# Power_Board.net
KiCad netlist of a schematic drawn in EAGLE
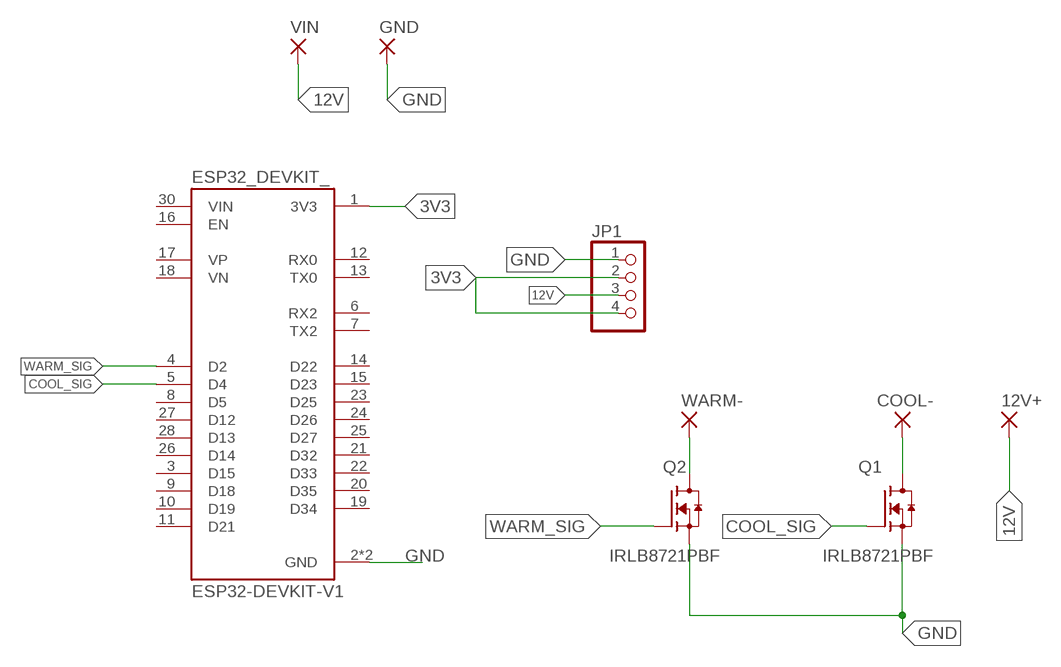
[diagram p0: schematic, sheet 1]

(export (version "E")
  (design (tool "Eeschema 10.0.6"))
  (components
    (comp (ref "12V+")
      (value "WIREPADSMD5-2,5")
      (footprint "eagle-import:5-2,5")
      (libsource (lib "eagle-import") (part "WIREPADSMD5-2,5"))
    )
    (comp (ref "COOL-")
      (value "WIREPADSMD5-2,5")
      (footprint "eagle-import:5-2,5")
      (libsource (lib "eagle-import") (part "WIREPADSMD5-2,5"))
    )
    (comp (ref "ESP32_DEVKIT_")
      (value "ESP32-DEVKIT-V1")
      (footprint "eagle-import:MODULE_ESP32_DEVKIT_V1")
      (fields (field (name "MF") "Do it"))
      (libsource (lib "eagle-import") (part "ESP32-DEVKIT-V1"))
    )
    (comp (ref "GND")
      (value "WIREPADSMD5-2,5")
      (footprint "eagle-import:5-2,5")
      (libsource (lib "eagle-import") (part "WIREPADSMD5-2,5"))
    )
    (comp (ref "JP1")
      (value "PINHD-1X4")
      (footprint "eagle-import:1X04")
      (libsource (lib "eagle-import") (part "PINHD-1X4"))
    )
    (comp (ref "Q1")
      (value "IRLB8721PBF")
      (footprint "eagle-import:TO254P1067X483X2057-3")
      (fields (field (name "MF") "Infineon Technologies"))
      (libsource (lib "eagle-import") (part "IRLB8721PBF"))
    )
    (comp (ref "Q2")
      (value "IRLB8721PBF")
      (footprint "eagle-import:TO254P1067X483X2057-3")
      (fields (field (name "MF") "Infineon Technologies"))
      (libsource (lib "eagle-import") (part "IRLB8721PBF"))
    )
    (comp (ref "VIN")
      (value "WIREPADSMD5-2,5")
      (footprint "eagle-import:5-2,5")
      (libsource (lib "eagle-import") (part "WIREPADSMD5-2,5"))
    )
    (comp (ref "WARM-")
      (value "WIREPADSMD5-2,5")
      (footprint "eagle-import:5-2,5")
      (libsource (lib "eagle-import") (part "WIREPADSMD5-2,5"))
    )
  )
  (nets
    (net (code "1") (name "3V3") (class "Default")
      (node (ref "ESP32_DEVKIT_") (pin "1") (pinfunction "3V3_1") (pintype "output"))
      (node (ref "JP1") (pin "2") (pinfunction "2_2") (pintype "passive"))
      (node (ref "JP1") (pin "4") (pinfunction "4_4") (pintype "passive"))
    )
    (net (code "2") (name "12V") (class "Default")
      (node (ref "12V+") (pin "1") (pinfunction "P_1") (pintype "passive"))
      (node (ref "JP1") (pin "3") (pinfunction "3_3") (pintype "passive"))
      (node (ref "VIN") (pin "1") (pinfunction "P_1") (pintype "passive"))
    )
    (net (code "3") (name "COOL_SIG") (class "Default")
      (node (ref "ESP32_DEVKIT_") (pin "5") (pinfunction "D4_5") (pintype "bidirectional"))
      (node (ref "Q1") (pin "1") (pinfunction "G_1") (pintype "passive"))
    )
    (net (code "4") (name "GND") (class "Default")
      (node (ref "ESP32_DEVKIT_") (pin "2") (pinfunction "GND_2") (pintype "power_in"))
      (node (ref "ESP32_DEVKIT_") (pin "29") (pinfunction "GND_29") (pintype "power_in"))
      (node (ref "GND") (pin "1") (pinfunction "P_1") (pintype "passive"))
      (node (ref "JP1") (pin "1") (pinfunction "1_1") (pintype "passive"))
      (node (ref "Q1") (pin "3") (pinfunction "S_3") (pintype "passive"))
      (node (ref "Q2") (pin "3") (pinfunction "S_3") (pintype "passive"))
    )
    (net (code "5") (name "Net-(COOL--P)") (class "Default")
      (node (ref "COOL-") (pin "1") (pinfunction "P_1") (pintype "passive"))
      (node (ref "Q1") (pin "2") (pinfunction "D_2") (pintype "passive"))
    )
    (net (code "6") (name "Net-(Q2-D)") (class "Default")
      (node (ref "Q2") (pin "2") (pinfunction "D_2") (pintype "passive"))
      (node (ref "WARM-") (pin "1") (pinfunction "P_1") (pintype "passive"))
    )
    (net (code "7") (name "WARM_SIG") (class "Default")
      (node (ref "ESP32_DEVKIT_") (pin "4") (pinfunction "D2_4") (pintype "bidirectional"))
      (node (ref "Q2") (pin "1") (pinfunction "G_1") (pintype "passive"))
    )
    (net (code "8") (name "unconnected-(ESP32_DEVKIT_-D5-Pad8)") (class "Default")
      (node (ref "ESP32_DEVKIT_") (pin "8") (pinfunction "D5_8") (pintype "bidirectional"))
    )
    (net (code "9") (name "unconnected-(ESP32_DEVKIT_-D12-Pad27)") (class "Default")
      (node (ref "ESP32_DEVKIT_") (pin "27") (pinfunction "D12_27") (pintype "bidirectional"))
    )
    (net (code "10") (name "unconnected-(ESP32_DEVKIT_-D13-Pad28)") (class "Default")
      (node (ref "ESP32_DEVKIT_") (pin "28") (pinfunction "D13_28") (pintype "bidirectional"))
    )
    (net (code "11") (name "unconnected-(ESP32_DEVKIT_-D14-Pad26)") (class "Default")
      (node (ref "ESP32_DEVKIT_") (pin "26") (pinfunction "D14_26") (pintype "bidirectional"))
    )
    (net (code "12") (name "unconnected-(ESP32_DEVKIT_-D15-Pad3)") (class "Default")
      (node (ref "ESP32_DEVKIT_") (pin "3") (pinfunction "D15_3") (pintype "bidirectional"))
    )
    (net (code "13") (name "unconnected-(ESP32_DEVKIT_-D18-Pad9)") (class "Default")
      (node (ref "ESP32_DEVKIT_") (pin "9") (pinfunction "D18_9") (pintype "bidirectional"))
    )
    (net (code "14") (name "unconnected-(ESP32_DEVKIT_-D19-Pad10)") (class "Default")
      (node (ref "ESP32_DEVKIT_") (pin "10") (pinfunction "D19_10") (pintype "bidirectional"))
    )
    (net (code "15") (name "unconnected-(ESP32_DEVKIT_-D21-Pad11)") (class "Default")
      (node (ref "ESP32_DEVKIT_") (pin "11") (pinfunction "D21_11") (pintype "bidirectional"))
    )
    (net (code "16") (name "unconnected-(ESP32_DEVKIT_-D22-Pad14)") (class "Default")
      (node (ref "ESP32_DEVKIT_") (pin "14") (pinfunction "D22_14") (pintype "bidirectional"))
    )
    (net (code "17") (name "unconnected-(ESP32_DEVKIT_-D23-Pad15)") (class "Default")
      (node (ref "ESP32_DEVKIT_") (pin "15") (pinfunction "D23_15") (pintype "bidirectional"))
    )
    (net (code "18") (name "unconnected-(ESP32_DEVKIT_-D25-Pad23)") (class "Default")
      (node (ref "ESP32_DEVKIT_") (pin "23") (pinfunction "D25_23") (pintype "bidirectional"))
    )
    (net (code "19") (name "unconnected-(ESP32_DEVKIT_-D26-Pad24)") (class "Default")
      (node (ref "ESP32_DEVKIT_") (pin "24") (pinfunction "D26_24") (pintype "bidirectional"))
    )
    (net (code "20") (name "unconnected-(ESP32_DEVKIT_-D27-Pad25)") (class "Default")
      (node (ref "ESP32_DEVKIT_") (pin "25") (pinfunction "D27_25") (pintype "bidirectional"))
    )
    (net (code "21") (name "unconnected-(ESP32_DEVKIT_-D32-Pad21)") (class "Default")
      (node (ref "ESP32_DEVKIT_") (pin "21") (pinfunction "D32_21") (pintype "bidirectional"))
    )
    (net (code "22") (name "unconnected-(ESP32_DEVKIT_-D33-Pad22)") (class "Default")
      (node (ref "ESP32_DEVKIT_") (pin "22") (pinfunction "D33_22") (pintype "bidirectional"))
    )
    (net (code "23") (name "unconnected-(ESP32_DEVKIT_-D34-Pad19)") (class "Default")
      (node (ref "ESP32_DEVKIT_") (pin "19") (pinfunction "D34_19") (pintype "bidirectional"))
    )
    (net (code "24") (name "unconnected-(ESP32_DEVKIT_-D35-Pad20)") (class "Default")
      (node (ref "ESP32_DEVKIT_") (pin "20") (pinfunction "D35_20") (pintype "bidirectional"))
    )
    (net (code "25") (name "unconnected-(ESP32_DEVKIT_-EN-Pad16)") (class "Default")
      (node (ref "ESP32_DEVKIT_") (pin "16") (pinfunction "EN_16") (pintype "input"))
    )
    (net (code "26") (name "unconnected-(ESP32_DEVKIT_-RX0-Pad12)") (class "Default")
      (node (ref "ESP32_DEVKIT_") (pin "12") (pinfunction "RX0_12") (pintype "input"))
    )
    (net (code "27") (name "unconnected-(ESP32_DEVKIT_-RX2-Pad6)") (class "Default")
      (node (ref "ESP32_DEVKIT_") (pin "6") (pinfunction "RX2_6") (pintype "input"))
    )
    (net (code "28") (name "unconnected-(ESP32_DEVKIT_-TX0-Pad13)") (class "Default")
      (node (ref "ESP32_DEVKIT_") (pin "13") (pinfunction "TX0_13") (pintype "output"))
    )
    (net (code "29") (name "unconnected-(ESP32_DEVKIT_-TX2-Pad7)") (class "Default")
      (node (ref "ESP32_DEVKIT_") (pin "7") (pinfunction "TX2_7") (pintype "output"))
    )
    (net (code "30") (name "unconnected-(ESP32_DEVKIT_-VIN-Pad30)") (class "Default")
      (node (ref "ESP32_DEVKIT_") (pin "30") (pinfunction "VIN_30") (pintype "input"))
    )
    (net (code "31") (name "unconnected-(ESP32_DEVKIT_-VN-Pad18)") (class "Default")
      (node (ref "ESP32_DEVKIT_") (pin "18") (pinfunction "VN_18") (pintype "bidirectional"))
    )
    (net (code "32") (name "unconnected-(ESP32_DEVKIT_-VP-Pad17)") (class "Default")
      (node (ref "ESP32_DEVKIT_") (pin "17") (pinfunction "VP_17") (pintype "bidirectional"))
    )
  )
)
